# HEAD_IO_RevB.net
KiCad netlist of a schematic drawn in EAGLE
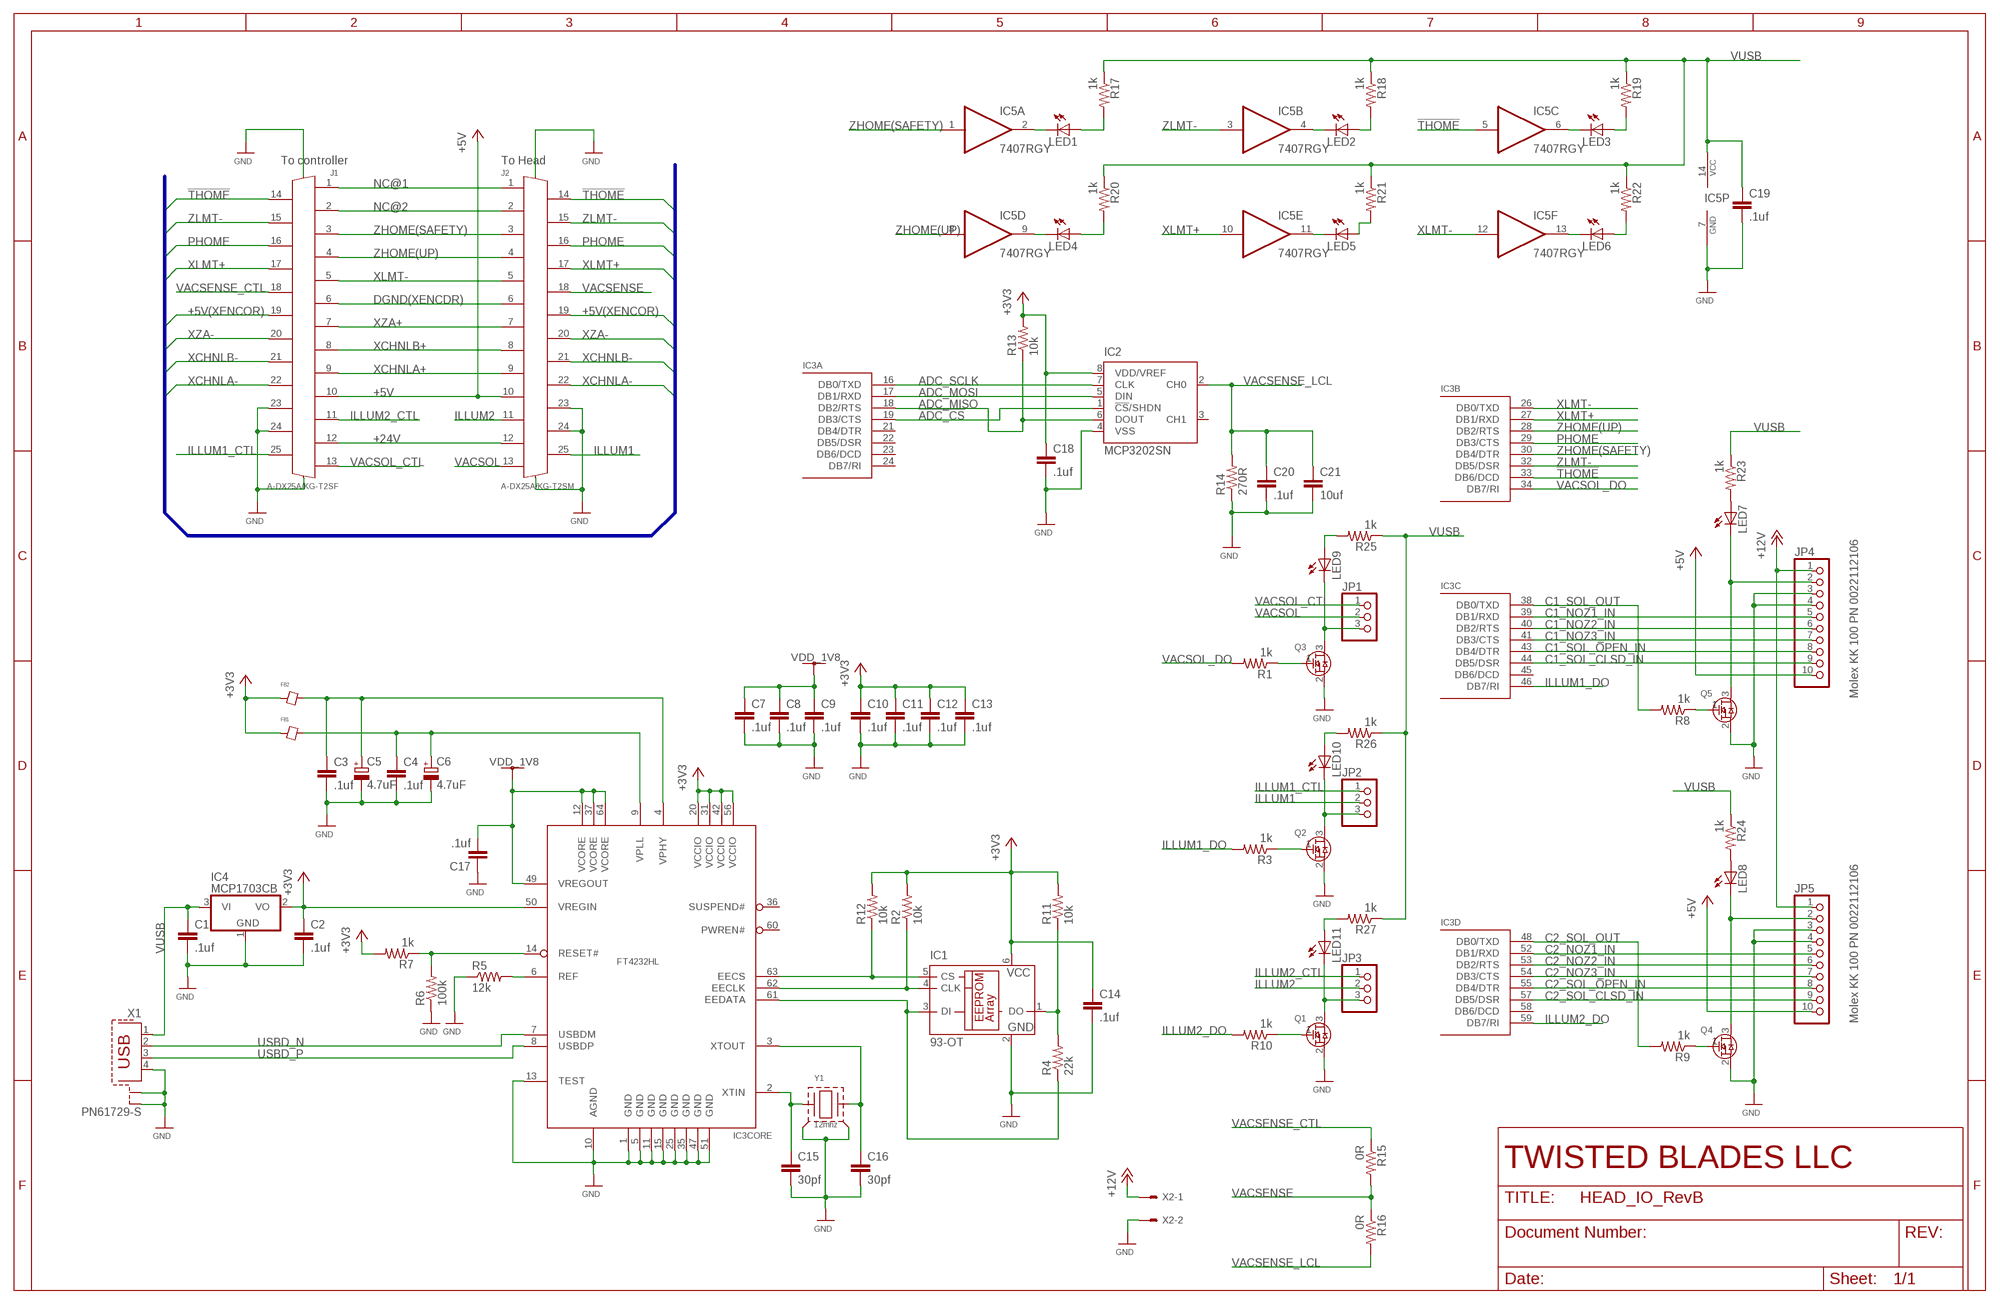
[diagram p0: schematic, sheet 1]

(export (version "E")
  (design (tool "Eeschema 10.0.6"))
  (components
    (comp (ref "C1")
      (value ".1uf")
      (footprint "eagle-import:C0603")
      (libsource (lib "eagle-import") (part "C-EUC0603"))
    )
    (comp (ref "C2")
      (value ".1uf")
      (footprint "eagle-import:C0603")
      (libsource (lib "eagle-import") (part "C-EUC0603"))
    )
    (comp (ref "C3")
      (value ".1uf")
      (footprint "eagle-import:C0603")
      (libsource (lib "eagle-import") (part "C-EUC0603"))
    )
    (comp (ref "C4")
      (value ".1uf")
      (footprint "eagle-import:C0603")
      (libsource (lib "eagle-import") (part "C-EUC0603"))
    )
    (comp (ref "C5")
      (value "4.7uF")
      (footprint "eagle-import:A_3216-18R")
      (libsource (lib "eagle-import") (part "CPOL-EUA/3216-18R"))
    )
    (comp (ref "C6")
      (value "4.7uF")
      (footprint "eagle-import:A_3216-18R")
      (libsource (lib "eagle-import") (part "CPOL-EUA/3216-18R"))
    )
    (comp (ref "C7")
      (value ".1uf")
      (footprint "eagle-import:C0603")
      (libsource (lib "eagle-import") (part "C-EUC0603"))
    )
    (comp (ref "C8")
      (value ".1uf")
      (footprint "eagle-import:C0603")
      (libsource (lib "eagle-import") (part "C-EUC0603"))
    )
    (comp (ref "C9")
      (value ".1uf")
      (footprint "eagle-import:C0603")
      (libsource (lib "eagle-import") (part "C-EUC0603"))
    )
    (comp (ref "C10")
      (value ".1uf")
      (footprint "eagle-import:C0603")
      (libsource (lib "eagle-import") (part "C-EUC0603"))
    )
    (comp (ref "C11")
      (value ".1uf")
      (footprint "eagle-import:C0603")
      (libsource (lib "eagle-import") (part "C-EUC0603"))
    )
    (comp (ref "C12")
      (value ".1uf")
      (footprint "eagle-import:C0603")
      (libsource (lib "eagle-import") (part "C-EUC0603"))
    )
    (comp (ref "C13")
      (value ".1uf")
      (footprint "eagle-import:C0603")
      (libsource (lib "eagle-import") (part "C-EUC0603"))
    )
    (comp (ref "C14")
      (value ".1uf")
      (footprint "eagle-import:C0603")
      (libsource (lib "eagle-import") (part "C-EUC0603"))
    )
    (comp (ref "C15")
      (value "30pf")
      (footprint "eagle-import:C0603")
      (libsource (lib "eagle-import") (part "C-EUC0603"))
    )
    (comp (ref "C16")
      (value "30pf")
      (footprint "eagle-import:C0603")
      (libsource (lib "eagle-import") (part "C-EUC0603"))
    )
    (comp (ref "C17")
      (value ".1uf")
      (footprint "eagle-import:C0603")
      (libsource (lib "eagle-import") (part "C-EUC0603"))
    )
    (comp (ref "C18")
      (value ".1uf")
      (footprint "eagle-import:C0603")
      (libsource (lib "eagle-import") (part "C-EUC0603"))
    )
    (comp (ref "C19")
      (value ".1uf")
      (footprint "eagle-import:C0603")
      (libsource (lib "eagle-import") (part "C-EUC0603"))
    )
    (comp (ref "C20")
      (value ".1uf")
      (footprint "eagle-import:C0603")
      (libsource (lib "eagle-import") (part "C-EUC0603"))
    )
    (comp (ref "C21")
      (value "10uf")
      (footprint "eagle-import:C0805K")
      (libsource (lib "eagle-import") (part "C-EUC0805K"))
    )
    (comp (ref "FB1")
      (value "FERRITE0603")
      (footprint "eagle-import:0603")
      (libsource (lib "eagle-import") (part "FERRITE0603"))
    )
    (comp (ref "FB2")
      (value "FERRITE0603")
      (footprint "eagle-import:0603")
      (libsource (lib "eagle-import") (part "FERRITE0603"))
    )
    (comp (ref "IC1")
      (value "93-OT")
      (footprint "eagle-import:SOT23-6")
      (libsource (lib "eagle-import") (part "93-OT"))
    )
    (comp (ref "IC2")
      (value "MCP3202SN")
      (footprint "eagle-import:SO-08")
      (libsource (lib "eagle-import") (part "MCP3202SN"))
    )
    (comp (ref "IC3")
      (value "FT4232HL")
      (footprint "eagle-import:LQFP64")
      (libsource (lib "eagle-import") (part "FT4232HL"))
    )
    (comp (ref "IC4")
      (value "MCP1703CB")
      (footprint "eagle-import:SOT23")
      (libsource (lib "eagle-import") (part "MCP1703CB"))
    )
    (comp (ref "IC5")
      (value "7407RGY")
      (footprint "eagle-import:TI_VQFN14")
      (libsource (lib "eagle-import") (part "7407RGY"))
    )
    (comp (ref "J1")
      (value "A-DX25A/KG-T2SF")
      (footprint "eagle-import:A-DF25A_KG-T2S")
      (libsource (lib "eagle-import") (part "A-DX25A/KG-T2SF"))
    )
    (comp (ref "J2")
      (value "A-DX25A/KG-T2SM")
      (footprint "eagle-import:A-DS25A_KG-T2S")
      (libsource (lib "eagle-import") (part "A-DX25A/KG-T2SM"))
    )
    (comp (ref "JP1")
      (value "PINHD-1X3")
      (footprint "eagle-import:1X03")
      (libsource (lib "eagle-import") (part "PINHD-1X3"))
    )
    (comp (ref "JP2")
      (value "PINHD-1X3")
      (footprint "eagle-import:1X03")
      (libsource (lib "eagle-import") (part "PINHD-1X3"))
    )
    (comp (ref "JP3")
      (value "PINHD-1X3")
      (footprint "eagle-import:1X03")
      (libsource (lib "eagle-import") (part "PINHD-1X3"))
    )
    (comp (ref "JP4")
      (value "PINHD-1X10")
      (footprint "eagle-import:1X10")
      (libsource (lib "eagle-import") (part "PINHD-1X10"))
    )
    (comp (ref "JP5")
      (value "PINHD-1X10")
      (footprint "eagle-import:1X10")
      (libsource (lib "eagle-import") (part "PINHD-1X10"))
    )
    (comp (ref "LED1")
      (value "LEDCHIP-LED0603")
      (footprint "eagle-import:CHIP-LED0603")
      (libsource (lib "eagle-import") (part "LEDCHIP-LED0603"))
    )
    (comp (ref "LED2")
      (value "LEDCHIP-LED0603")
      (footprint "eagle-import:CHIP-LED0603")
      (libsource (lib "eagle-import") (part "LEDCHIP-LED0603"))
    )
    (comp (ref "LED3")
      (value "LEDCHIP-LED0603")
      (footprint "eagle-import:CHIP-LED0603")
      (libsource (lib "eagle-import") (part "LEDCHIP-LED0603"))
    )
    (comp (ref "LED4")
      (value "LEDCHIP-LED0603")
      (footprint "eagle-import:CHIP-LED0603")
      (libsource (lib "eagle-import") (part "LEDCHIP-LED0603"))
    )
    (comp (ref "LED5")
      (value "LEDCHIP-LED0603")
      (footprint "eagle-import:CHIP-LED0603")
      (libsource (lib "eagle-import") (part "LEDCHIP-LED0603"))
    )
    (comp (ref "LED6")
      (value "LEDCHIP-LED0603")
      (footprint "eagle-import:CHIP-LED0603")
      (libsource (lib "eagle-import") (part "LEDCHIP-LED0603"))
    )
    (comp (ref "LED7")
      (value "LEDCHIP-LED0603")
      (footprint "eagle-import:CHIP-LED0603")
      (libsource (lib "eagle-import") (part "LEDCHIP-LED0603"))
    )
    (comp (ref "LED8")
      (value "LEDCHIP-LED0603")
      (footprint "eagle-import:CHIP-LED0603")
      (libsource (lib "eagle-import") (part "LEDCHIP-LED0603"))
    )
    (comp (ref "LED9")
      (value "LEDCHIP-LED0603")
      (footprint "eagle-import:CHIP-LED0603")
      (libsource (lib "eagle-import") (part "LEDCHIP-LED0603"))
    )
    (comp (ref "LED10")
      (value "LEDCHIP-LED0603")
      (footprint "eagle-import:CHIP-LED0603")
      (libsource (lib "eagle-import") (part "LEDCHIP-LED0603"))
    )
    (comp (ref "LED11")
      (value "LEDCHIP-LED0603")
      (footprint "eagle-import:CHIP-LED0603")
      (libsource (lib "eagle-import") (part "LEDCHIP-LED0603"))
    )
    (comp (ref "Q1")
      (value "FDN86246")
      (footprint "eagle-import:SOT23C")
      (libsource (lib "eagle-import") (part "FDN86246"))
    )
    (comp (ref "Q2")
      (value "FDN86246")
      (footprint "eagle-import:SOT23C")
      (libsource (lib "eagle-import") (part "FDN86246"))
    )
    (comp (ref "Q3")
      (value "FDN86246")
      (footprint "eagle-import:SOT23C")
      (libsource (lib "eagle-import") (part "FDN86246"))
    )
    (comp (ref "Q4")
      (value "FDN86246")
      (footprint "eagle-import:SOT23C")
      (libsource (lib "eagle-import") (part "FDN86246"))
    )
    (comp (ref "Q5")
      (value "FDN86246")
      (footprint "eagle-import:SOT23C")
      (libsource (lib "eagle-import") (part "FDN86246"))
    )
    (comp (ref "R1")
      (value "1k")
      (footprint "eagle-import:R0603")
      (libsource (lib "eagle-import") (part "R-US_R0603"))
    )
    (comp (ref "R2")
      (value "10k")
      (footprint "eagle-import:R0603")
      (libsource (lib "eagle-import") (part "R-US_R0603"))
    )
    (comp (ref "R3")
      (value "1k")
      (footprint "eagle-import:R0603")
      (libsource (lib "eagle-import") (part "R-US_R0603"))
    )
    (comp (ref "R4")
      (value "22k")
      (footprint "eagle-import:R0603")
      (libsource (lib "eagle-import") (part "R-US_R0603"))
    )
    (comp (ref "R5")
      (value "12k")
      (footprint "eagle-import:R0603")
      (libsource (lib "eagle-import") (part "R-US_R0603"))
    )
    (comp (ref "R6")
      (value "100k")
      (footprint "eagle-import:R0603")
      (libsource (lib "eagle-import") (part "R-US_R0603"))
    )
    (comp (ref "R7")
      (value "1k")
      (footprint "eagle-import:R0603")
      (libsource (lib "eagle-import") (part "R-US_R0603"))
    )
    (comp (ref "R8")
      (value "1k")
      (footprint "eagle-import:R0603")
      (libsource (lib "eagle-import") (part "R-US_R0603"))
    )
    (comp (ref "R9")
      (value "1k")
      (footprint "eagle-import:R0603")
      (libsource (lib "eagle-import") (part "R-US_R0603"))
    )
    (comp (ref "R10")
      (value "1k")
      (footprint "eagle-import:R0603")
      (libsource (lib "eagle-import") (part "R-US_R0603"))
    )
    (comp (ref "R11")
      (value "10k")
      (footprint "eagle-import:R0603")
      (libsource (lib "eagle-import") (part "R-US_R0603"))
    )
    (comp (ref "R12")
      (value "10k")
      (footprint "eagle-import:R0603")
      (libsource (lib "eagle-import") (part "R-US_R0603"))
    )
    (comp (ref "R13")
      (value "10k")
      (footprint "eagle-import:R0603")
      (libsource (lib "eagle-import") (part "R-US_R0603"))
    )
    (comp (ref "R14")
      (value "270R")
      (footprint "eagle-import:R0603")
      (libsource (lib "eagle-import") (part "R-US_R0603"))
    )
    (comp (ref "R15")
      (value "0R")
      (footprint "eagle-import:R0603")
      (libsource (lib "eagle-import") (part "R-US_R0603"))
    )
    (comp (ref "R16")
      (value "0R")
      (footprint "eagle-import:R0603")
      (libsource (lib "eagle-import") (part "R-US_R0603"))
    )
    (comp (ref "R17")
      (value "1k")
      (footprint "eagle-import:R0603")
      (libsource (lib "eagle-import") (part "R-US_R0603"))
    )
    (comp (ref "R18")
      (value "1k")
      (footprint "eagle-import:R0603")
      (libsource (lib "eagle-import") (part "R-US_R0603"))
    )
    (comp (ref "R19")
      (value "1k")
      (footprint "eagle-import:R0603")
      (libsource (lib "eagle-import") (part "R-US_R0603"))
    )
    (comp (ref "R20")
      (value "1k")
      (footprint "eagle-import:R0603")
      (libsource (lib "eagle-import") (part "R-US_R0603"))
    )
    (comp (ref "R21")
      (value "1k")
      (footprint "eagle-import:R0603")
      (libsource (lib "eagle-import") (part "R-US_R0603"))
    )
    (comp (ref "R22")
      (value "1k")
      (footprint "eagle-import:R0603")
      (libsource (lib "eagle-import") (part "R-US_R0603"))
    )
    (comp (ref "R23")
      (value "1k")
      (footprint "eagle-import:R0603")
      (libsource (lib "eagle-import") (part "R-US_R0603"))
    )
    (comp (ref "R24")
      (value "1k")
      (footprint "eagle-import:R0603")
      (libsource (lib "eagle-import") (part "R-US_R0603"))
    )
    (comp (ref "R25")
      (value "1k")
      (footprint "eagle-import:R0603")
      (libsource (lib "eagle-import") (part "R-US_R0603"))
    )
    (comp (ref "R26")
      (value "1k")
      (footprint "eagle-import:R0603")
      (libsource (lib "eagle-import") (part "R-US_R0603"))
    )
    (comp (ref "R27")
      (value "1k")
      (footprint "eagle-import:R0603")
      (libsource (lib "eagle-import") (part "R-US_R0603"))
    )
    (comp (ref "X1")
      (value "PN61729-S")
      (footprint "eagle-import:PN61729-S")
      (libsource (lib "eagle-import") (part "PN61729-S"))
    )
    (comp (ref "X2")
      (value "KK-156-2")
      (footprint "eagle-import:KK-156-2")
      (fields (field (name "DIGIKEYPN") "WM50008-02-ND "))
      (libsource (lib "eagle-import") (part "KK-156-2"))
    )
    (comp (ref "Y1")
      (value "12mhz")
      (footprint "eagle-import:ABM8G")
      (libsource (lib "eagle-import") (part "ABM8G"))
    )
  )
  (nets
    (net (code "1") (name "+3V3") (class "Default")
      (node (ref "C10") (pin "1") (pinfunction "1_1") (pintype "passive"))
      (node (ref "C11") (pin "1") (pinfunction "1_1") (pintype "passive"))
      (node (ref "C12") (pin "1") (pinfunction "1_1") (pintype "passive"))
      (node (ref "C13") (pin "1") (pinfunction "1_1") (pintype "passive"))
      (node (ref "C14") (pin "1") (pinfunction "1_1") (pintype "passive"))
      (node (ref "C18") (pin "1") (pinfunction "1_1") (pintype "passive"))
      (node (ref "C2") (pin "1") (pinfunction "1_1") (pintype "passive"))
      (node (ref "FB1") (pin "P$1") (pinfunction "P$1_P$1") (pintype "bidirectional"))
      (node (ref "FB2") (pin "P$1") (pinfunction "P$1_P$1") (pintype "bidirectional"))
      (node (ref "IC1") (pin "6") (pinfunction "VCC_6") (pintype "power_in"))
      (node (ref "IC2") (pin "8") (pinfunction "VDD/VREF_8") (pintype "input"))
      (node (ref "IC3") (pin "20") (pinfunction "VCCIO_20") (pintype "power_in"))
      (node (ref "IC3") (pin "31") (pinfunction "VCCIO_31") (pintype "power_in"))
      (node (ref "IC3") (pin "42") (pinfunction "VCCIO_42") (pintype "power_in"))
      (node (ref "IC3") (pin "50") (pinfunction "VREGIN_50") (pintype "bidirectional"))
      (node (ref "IC3") (pin "56") (pinfunction "VCCIO_56") (pintype "power_in"))
      (node (ref "IC4") (pin "2") (pinfunction "VO_2") (pintype "passive"))
      (node (ref "R11") (pin "2") (pinfunction "2_2") (pintype "passive"))
      (node (ref "R12") (pin "2") (pinfunction "2_2") (pintype "passive"))
      (node (ref "R13") (pin "2") (pinfunction "2_2") (pintype "passive"))
      (node (ref "R2") (pin "2") (pinfunction "2_2") (pintype "passive"))
      (node (ref "R7") (pin "2") (pinfunction "2_2") (pintype "passive"))
    )
    (net (code "2") (name "+5V") (class "Default")
      (node (ref "J1") (pin "10") (pinfunction "10_10") (pintype "bidirectional"))
      (node (ref "J2") (pin "10") (pinfunction "10_10") (pintype "bidirectional"))
      (node (ref "JP4") (pin "10") (pinfunction "10_10") (pintype "passive"))
      (node (ref "JP5") (pin "10") (pinfunction "10_10") (pintype "passive"))
    )
    (net (code "3") (name "+12V") (class "Default")
      (node (ref "JP4") (pin "1") (pinfunction "1_1") (pintype "passive"))
      (node (ref "JP5") (pin "1") (pinfunction "1_1") (pintype "passive"))
      (node (ref "X2") (pin "1") (pinfunction "S_1") (pintype "passive"))
    )
    (net (code "4") (name "/+5V(XENCOR)") (class "Default")
      (node (ref "J1") (pin "19") (pinfunction "19_19") (pintype "bidirectional"))
      (node (ref "J2") (pin "19") (pinfunction "19_19") (pintype "bidirectional"))
    )
    (net (code "5") (name "/+24V") (class "Default")
      (node (ref "J1") (pin "12") (pinfunction "12_12") (pintype "bidirectional"))
      (node (ref "J2") (pin "12") (pinfunction "12_12") (pintype "bidirectional"))
    )
    (net (code "6") (name "/ADC_MISO") (class "Default")
      (node (ref "IC2") (pin "6") (pinfunction "DOUT_6") (pintype "input"))
      (node (ref "IC3") (pin "18") (pinfunction "DB2/RTS_18") (pintype "bidirectional"))
      (node (ref "R13") (pin "1") (pinfunction "1_1") (pintype "passive"))
    )
    (net (code "7") (name "/ADC_MOSI") (class "Default")
      (node (ref "IC2") (pin "5") (pinfunction "DIN_5") (pintype "input"))
      (node (ref "IC3") (pin "17") (pinfunction "DB1/RXD_17") (pintype "bidirectional"))
    )
    (net (code "8") (name "/ADC_SCLK") (class "Default")
      (node (ref "IC2") (pin "7") (pinfunction "CLK_7") (pintype "input"))
      (node (ref "IC3") (pin "16") (pinfunction "DB0/TXD_16") (pintype "bidirectional"))
    )
    (net (code "9") (name "/C1_NOZ1_IN") (class "Default")
      (node (ref "IC3") (pin "39") (pinfunction "DB1/RXD_39") (pintype "bidirectional"))
      (node (ref "JP4") (pin "5") (pinfunction "5_5") (pintype "passive"))
    )
    (net (code "10") (name "/C1_NOZ2_IN") (class "Default")
      (node (ref "IC3") (pin "40") (pinfunction "DB2/RTS_40") (pintype "bidirectional"))
      (node (ref "JP4") (pin "6") (pinfunction "6_6") (pintype "passive"))
    )
    (net (code "11") (name "/C1_NOZ3_IN") (class "Default")
      (node (ref "IC3") (pin "41") (pinfunction "DB3/CTS_41") (pintype "bidirectional"))
      (node (ref "JP4") (pin "7") (pinfunction "7_7") (pintype "passive"))
    )
    (net (code "12") (name "/C1_SOL_CLSD_IN") (class "Default")
      (node (ref "IC3") (pin "44") (pinfunction "DB5/DSR_44") (pintype "bidirectional"))
      (node (ref "JP4") (pin "9") (pinfunction "9_9") (pintype "passive"))
    )
    (net (code "13") (name "/C1_SOL_OPEN_IN") (class "Default")
      (node (ref "IC3") (pin "43") (pinfunction "DB4/DTR_43") (pintype "bidirectional"))
      (node (ref "JP4") (pin "8") (pinfunction "8_8") (pintype "passive"))
    )
    (net (code "14") (name "/C1_SOL_OUT") (class "Default")
      (node (ref "IC3") (pin "38") (pinfunction "DB0/TXD_38") (pintype "bidirectional"))
      (node (ref "R8") (pin "2") (pinfunction "2_2") (pintype "passive"))
    )
    (net (code "15") (name "/C2_NOZ1_IN") (class "Default")
      (node (ref "IC3") (pin "52") (pinfunction "DB1/RXD_52") (pintype "bidirectional"))
      (node (ref "JP5") (pin "5") (pinfunction "5_5") (pintype "passive"))
    )
    (net (code "16") (name "/C2_NOZ2_IN") (class "Default")
      (node (ref "IC3") (pin "53") (pinfunction "DB2/RTS_53") (pintype "bidirectional"))
      (node (ref "JP5") (pin "6") (pinfunction "6_6") (pintype "passive"))
    )
    (net (code "17") (name "/C2_NOZ3_IN") (class "Default")
      (node (ref "IC3") (pin "54") (pinfunction "DB3/CTS_54") (pintype "bidirectional"))
      (node (ref "JP5") (pin "7") (pinfunction "7_7") (pintype "passive"))
    )
    (net (code "18") (name "/C2_SOL_CLSD_IN") (class "Default")
      (node (ref "IC3") (pin "57") (pinfunction "DB5/DSR_57") (pintype "bidirectional"))
      (node (ref "JP5") (pin "9") (pinfunction "9_9") (pintype "passive"))
    )
    (net (code "19") (name "/C2_SOL_OPEN_IN") (class "Default")
      (node (ref "IC3") (pin "55") (pinfunction "DB4/DTR_55") (pintype "bidirectional"))
      (node (ref "JP5") (pin "8") (pinfunction "8_8") (pintype "passive"))
    )
    (net (code "20") (name "/C2_SOL_OUT") (class "Default")
      (node (ref "IC3") (pin "48") (pinfunction "DB0/TXD_48") (pintype "bidirectional"))
      (node (ref "R9") (pin "2") (pinfunction "2_2") (pintype "passive"))
    )
    (net (code "21") (name "/DGND(XENCDR)") (class "Default")
      (node (ref "J1") (pin "6") (pinfunction "6_6") (pintype "bidirectional"))
      (node (ref "J2") (pin "6") (pinfunction "6_6") (pintype "bidirectional"))
    )
    (net (code "22") (name "/ILLUM1") (class "Default")
      (node (ref "J2") (pin "25") (pinfunction "25_25") (pintype "bidirectional"))
      (node (ref "JP2") (pin "2") (pinfunction "2_2") (pintype "passive"))
    )
    (net (code "23") (name "/ILLUM1_CTL") (class "Default")
      (node (ref "J1") (pin "25") (pinfunction "25_25") (pintype "bidirectional"))
      (node (ref "JP2") (pin "1") (pinfunction "1_1") (pintype "passive"))
    )
    (net (code "24") (name "/ILLUM1_DO") (class "Default")
      (node (ref "IC3") (pin "46") (pinfunction "DB7/RI_46") (pintype "bidirectional"))
      (node (ref "R3") (pin "2") (pinfunction "2_2") (pintype "passive"))
    )
    (net (code "25") (name "/ILLUM2") (class "Default")
      (node (ref "J2") (pin "11") (pinfunction "11_11") (pintype "bidirectional"))
      (node (ref "JP3") (pin "2") (pinfunction "2_2") (pintype "passive"))
    )
    (net (code "26") (name "/ILLUM2_CTL") (class "Default")
      (node (ref "J1") (pin "11") (pinfunction "11_11") (pintype "bidirectional"))
      (node (ref "JP3") (pin "1") (pinfunction "1_1") (pintype "passive"))
    )
    (net (code "27") (name "/ILLUM2_DO") (class "Default")
      (node (ref "IC3") (pin "59") (pinfunction "DB7/RI_59") (pintype "bidirectional"))
      (node (ref "R10") (pin "2") (pinfunction "2_2") (pintype "passive"))
    )
    (net (code "28") (name "/NC@1") (class "Default")
      (node (ref "J1") (pin "1") (pinfunction "1_1") (pintype "bidirectional"))
      (node (ref "J2") (pin "1") (pinfunction "1_1") (pintype "bidirectional"))
    )
    (net (code "29") (name "/NC@2") (class "Default")
      (node (ref "J1") (pin "2") (pinfunction "2_2") (pintype "bidirectional"))
      (node (ref "J2") (pin "2") (pinfunction "2_2") (pintype "bidirectional"))
    )
    (net (code "30") (name "/PHOME") (class "Default")
      (node (ref "IC3") (pin "29") (pinfunction "DB3/CTS_29") (pintype "bidirectional"))
      (node (ref "J1") (pin "16") (pinfunction "16_16") (pintype "bidirectional"))
      (node (ref "J2") (pin "16") (pinfunction "16_16") (pintype "bidirectional"))
    )
    (net (code "31") (name "/USBD_N") (class "Default")
      (node (ref "IC3") (pin "7") (pinfunction "USBDM_7") (pintype "input"))
      (node (ref "X1") (pin "2") (pinfunction "2_2") (pintype "passive"))
    )
    (net (code "32") (name "/USBD_P") (class "Default")
      (node (ref "IC3") (pin "8") (pinfunction "USBDP_8") (pintype "input"))
      (node (ref "X1") (pin "3") (pinfunction "3_3") (pintype "passive"))
    )
    (net (code "33") (name "/VACSENSE") (class "Default")
      (node (ref "J2") (pin "18") (pinfunction "18_18") (pintype "bidirectional"))
      (node (ref "R15") (pin "2") (pinfunction "2_2") (pintype "passive"))
      (node (ref "R16") (pin "1") (pinfunction "1_1") (pintype "passive"))
    )
    (net (code "34") (name "/VACSENSE_CTL") (class "Default")
      (node (ref "J1") (pin "18") (pinfunction "18_18") (pintype "bidirectional"))
      (node (ref "R15") (pin "1") (pinfunction "1_1") (pintype "passive"))
    )
    (net (code "35") (name "/VACSENSE_LCL") (class "Default")
      (node (ref "C20") (pin "1") (pinfunction "1_1") (pintype "passive"))
      (node (ref "C21") (pin "1") (pinfunction "1_1") (pintype "passive"))
      (node (ref "IC2") (pin "2") (pinfunction "CH0_2") (pintype "input"))
      (node (ref "R14") (pin "2") (pinfunction "2_2") (pintype "passive"))
      (node (ref "R16") (pin "2") (pinfunction "2_2") (pintype "passive"))
    )
    (net (code "36") (name "/VACSOL") (class "Default")
      (node (ref "J2") (pin "13") (pinfunction "13_13") (pintype "bidirectional"))
      (node (ref "JP1") (pin "2") (pinfunction "2_2") (pintype "passive"))
    )
    (net (code "37") (name "/VACSOL_CTL") (class "Default")
      (node (ref "J1") (pin "13") (pinfunction "13_13") (pintype "bidirectional"))
      (node (ref "JP1") (pin "1") (pinfunction "1_1") (pintype "passive"))
    )
    (net (code "38") (name "/VACSOL_DO") (class "Default")
      (node (ref "IC3") (pin "34") (pinfunction "DB7/RI_34") (pintype "bidirectional"))
      (node (ref "R1") (pin "2") (pinfunction "2_2") (pintype "passive"))
    )
    (net (code "39") (name "/VUSB") (class "Default")
      (node (ref "C1") (pin "1") (pinfunction "1_1") (pintype "passive"))
      (node (ref "C19") (pin "1") (pinfunction "1_1") (pintype "passive"))
      (node (ref "IC4") (pin "3") (pinfunction "VI_3") (pintype "input"))
      (node (ref "IC5") (pin "14") (pinfunction "VCC_14") (pintype "power_in"))
      (node (ref "R17") (pin "1") (pinfunction "1_1") (pintype "passive"))
      (node (ref "R18") (pin "1") (pinfunction "1_1") (pintype "passive"))
      (node (ref "R19") (pin "1") (pinfunction "1_1") (pintype "passive"))
      (node (ref "R20") (pin "1") (pinfunction "1_1") (pintype "passive"))
      (node (ref "R21") (pin "1") (pinfunction "1_1") (pintype "passive"))
      (node (ref "R22") (pin "1") (pinfunction "1_1") (pintype "passive"))
      (node (ref "R23") (pin "1") (pinfunction "1_1") (pintype "passive"))
      (node (ref "R24") (pin "1") (pinfunction "1_1") (pintype "passive"))
      (node (ref "R25") (pin "1") (pinfunction "1_1") (pintype "passive"))
      (node (ref "R26") (pin "1") (pinfunction "1_1") (pintype "passive"))
      (node (ref "R27") (pin "1") (pinfunction "1_1") (pintype "passive"))
      (node (ref "X1") (pin "1") (pinfunction "1_1") (pintype "passive"))
    )
    (net (code "40") (name "/XCHNLA+") (class "Default")
      (node (ref "J1") (pin "9") (pinfunction "9_9") (pintype "bidirectional"))
      (node (ref "J2") (pin "9") (pinfunction "9_9") (pintype "bidirectional"))
    )
    (net (code "41") (name "/XCHNLA-") (class "Default")
      (node (ref "J1") (pin "22") (pinfunction "22_22") (pintype "bidirectional"))
      (node (ref "J2") (pin "22") (pinfunction "22_22") (pintype "bidirectional"))
    )
    (net (code "42") (name "/XCHNLB+") (class "Default")
      (node (ref "J1") (pin "8") (pinfunction "8_8") (pintype "bidirectional"))
      (node (ref "J2") (pin "8") (pinfunction "8_8") (pintype "bidirectional"))
    )
    (net (code "43") (name "/XCHNLB-") (class "Default")
      (node (ref "J1") (pin "21") (pinfunction "21_21") (pintype "bidirectional"))
      (node (ref "J2") (pin "21") (pinfunction "21_21") (pintype "bidirectional"))
    )
    (net (code "44") (name "/XLMT+") (class "Default")
      (node (ref "IC3") (pin "27") (pinfunction "DB1/RXD_27") (pintype "bidirectional"))
      (node (ref "IC5") (pin "10") (pinfunction "I_10") (pintype "input"))
      (node (ref "J1") (pin "17") (pinfunction "17_17") (pintype "bidirectional"))
      (node (ref "J2") (pin "17") (pinfunction "17_17") (pintype "bidirectional"))
    )
    (net (code "45") (name "/XLMT-") (class "Default")
      (node (ref "IC3") (pin "26") (pinfunction "DB0/TXD_26") (pintype "bidirectional"))
      (node (ref "IC5") (pin "12") (pinfunction "I_12") (pintype "input"))
      (node (ref "J1") (pin "5") (pinfunction "5_5") (pintype "bidirectional"))
      (node (ref "J2") (pin "5") (pinfunction "5_5") (pintype "bidirectional"))
    )
    (net (code "46") (name "/XZA+") (class "Default")
      (node (ref "J1") (pin "7") (pinfunction "7_7") (pintype "bidirectional"))
      (node (ref "J2") (pin "7") (pinfunction "7_7") (pintype "bidirectional"))
    )
    (net (code "47") (name "/XZA-") (class "Default")
      (node (ref "J1") (pin "20") (pinfunction "20_20") (pintype "bidirectional"))
      (node (ref "J2") (pin "20") (pinfunction "20_20") (pintype "bidirectional"))
    )
    (net (code "48") (name "/ZHOME(SAFETY)") (class "Default")
      (node (ref "IC3") (pin "30") (pinfunction "DB4/DTR_30") (pintype "bidirectional"))
      (node (ref "IC5") (pin "1") (pinfunction "I_1") (pintype "input"))
      (node (ref "J1") (pin "3") (pinfunction "3_3") (pintype "bidirectional"))
      (node (ref "J2") (pin "3") (pinfunction "3_3") (pintype "bidirectional"))
    )
    (net (code "49") (name "/ZHOME(UP)") (class "Default")
      (node (ref "IC3") (pin "28") (pinfunction "DB2/RTS_28") (pintype "bidirectional"))
      (node (ref "IC5") (pin "8") (pinfunction "I_8") (pintype "input"))
      (node (ref "J1") (pin "4") (pinfunction "4_4") (pintype "bidirectional"))
      (node (ref "J2") (pin "4") (pinfunction "4_4") (pintype "bidirectional"))
    )
    (net (code "50") (name "/ZLMT-") (class "Default")
      (node (ref "IC3") (pin "32") (pinfunction "DB5/DSR_32") (pintype "bidirectional"))
      (node (ref "IC5") (pin "3") (pinfunction "I_3") (pintype "input"))
      (node (ref "J1") (pin "15") (pinfunction "15_15") (pintype "bidirectional"))
      (node (ref "J2") (pin "15") (pinfunction "15_15") (pintype "bidirectional"))
    )
    (net (code "51") (name "/~{ADC_CS}") (class "Default")
      (node (ref "IC2") (pin "1") (pinfunction "~{CS}/SHDN_1") (pintype "input"))
      (node (ref "IC3") (pin "19") (pinfunction "DB3/CTS_19") (pintype "bidirectional"))
    )
    (net (code "52") (name "/~{THOME}") (class "Default")
      (node (ref "IC3") (pin "33") (pinfunction "DB6/DCD_33") (pintype "bidirectional"))
      (node (ref "IC5") (pin "5") (pinfunction "I_5") (pintype "input"))
      (node (ref "J1") (pin "14") (pinfunction "14_14") (pintype "bidirectional"))
      (node (ref "J2") (pin "14") (pinfunction "14_14") (pintype "bidirectional"))
    )
    (net (code "53") (name "GND") (class "Default")
      (node (ref "C1") (pin "2") (pinfunction "2_2") (pintype "passive"))
      (node (ref "C10") (pin "2") (pinfunction "2_2") (pintype "passive"))
      (node (ref "C11") (pin "2") (pinfunction "2_2") (pintype "passive"))
      (node (ref "C12") (pin "2") (pinfunction "2_2") (pintype "passive"))
      (node (ref "C13") (pin "2") (pinfunction "2_2") (pintype "passive"))
      (node (ref "C14") (pin "2") (pinfunction "2_2") (pintype "passive"))
      (node (ref "C15") (pin "2") (pinfunction "2_2") (pintype "passive"))
      (node (ref "C16") (pin "2") (pinfunction "2_2") (pintype "passive"))
      (node (ref "C17") (pin "1") (pinfunction "1_1") (pintype "passive"))
      (node (ref "C18") (pin "2") (pinfunction "2_2") (pintype "passive"))
      (node (ref "C19") (pin "2") (pinfunction "2_2") (pintype "passive"))
      (node (ref "C2") (pin "2") (pinfunction "2_2") (pintype "passive"))
      (node (ref "C20") (pin "2") (pinfunction "2_2") (pintype "passive"))
      (node (ref "C21") (pin "2") (pinfunction "2_2") (pintype "passive"))
      (node (ref "C3") (pin "2") (pinfunction "2_2") (pintype "passive"))
      (node (ref "C4") (pin "2") (pinfunction "2_2") (pintype "passive"))
      (node (ref "C5") (pin "-") (pinfunction "-_-") (pintype "passive"))
      (node (ref "C6") (pin "-") (pinfunction "-_-") (pintype "passive"))
      (node (ref "C7") (pin "2") (pinfunction "2_2") (pintype "passive"))
      (node (ref "C8") (pin "2") (pinfunction "2_2") (pintype "passive"))
      (node (ref "C9") (pin "2") (pinfunction "2_2") (pintype "passive"))
      (node (ref "IC1") (pin "2") (pinfunction "GND_2") (pintype "power_in"))
      (node (ref "IC2") (pin "4") (pinfunction "VSS_4") (pintype "input"))
      (node (ref "IC3") (pin "1") (pinfunction "GND_1") (pintype "power_in"))
      (node (ref "IC3") (pin "10") (pinfunction "AGND_10") (pintype "power_in"))
      (node (ref "IC3") (pin "11") (pinfunction "GND_11") (pintype "power_in"))
      (node (ref "IC3") (pin "13") (pinfunction "TEST_13") (pintype "input"))
      (node (ref "IC3") (pin "15") (pinfunction "GND_15") (pintype "power_in"))
      (node (ref "IC3") (pin "25") (pinfunction "GND_25") (pintype "power_in"))
      (node (ref "IC3") (pin "35") (pinfunction "GND_35") (pintype "power_in"))
      (node (ref "IC3") (pin "47") (pinfunction "GND_47") (pintype "power_in"))
      (node (ref "IC3") (pin "5") (pinfunction "GND_5") (pintype "power_in"))
      (node (ref "IC3") (pin "51") (pinfunction "GND_51") (pintype "power_in"))
      (node (ref "IC4") (pin "1") (pinfunction "GND_1") (pintype "passive"))
      (node (ref "IC5") (pin "7") (pinfunction "GND_7") (pintype "power_in"))
      (node (ref "J1") (pin "23") (pinfunction "23_23") (pintype "bidirectional"))
      (node (ref "J1") (pin "24") (pinfunction "24_24") (pintype "bidirectional"))
      (node (ref "J1") (pin "SHLD@1") (pinfunction "SHLD_SHLD@1") (pintype "bidirectional"))
      (node (ref "J1") (pin "SHLD@2") (pinfunction "SHLD_SHLD@2") (pintype "bidirectional"))
      (node (ref "J2") (pin "23") (pinfunction "23_23") (pintype "bidirectional"))
      (node (ref "J2") (pin "24") (pinfunction "24_24") (pintype "bidirectional"))
      (node (ref "J2") (pin "SHLD@1") (pinfunction "SHLD_SHLD@1") (pintype "bidirectional"))
      (node (ref "J2") (pin "SHLD@2") (pinfunction "SHLD_SHLD@2") (pintype "bidirectional"))
      (node (ref "JP4") (pin "3") (pinfunction "3_3") (pintype "passive"))
      (node (ref "JP4") (pin "4") (pinfunction "4_4") (pintype "passive"))
      (node (ref "JP5") (pin "3") (pinfunction "3_3") (pintype "passive"))
      (node (ref "JP5") (pin "4") (pinfunction "4_4") (pintype "passive"))
      (node (ref "Q1") (pin "2") (pinfunction "S_2") (pintype "bidirectional"))
      (node (ref "Q2") (pin "2") (pinfunction "S_2") (pintype "bidirectional"))
      (node (ref "Q3") (pin "2") (pinfunction "S_2") (pintype "bidirectional"))
      (node (ref "Q4") (pin "2") (pinfunction "S_2") (pintype "bidirectional"))
      (node (ref "Q5") (pin "2") (pinfunction "S_2") (pintype "bidirectional"))
      (node (ref "R14") (pin "1") (pinfunction "1_1") (pintype "passive"))
      (node (ref "R5") (pin "1") (pinfunction "1_1") (pintype "passive"))
      (node (ref "R6") (pin "1") (pinfunction "1_1") (pintype "passive"))
      (node (ref "X1") (pin "4") (pinfunction "4_4") (pintype "passive"))
      (node (ref "X1") (pin "S1") (pinfunction "S1_S1") (pintype "passive"))
      (node (ref "X1") (pin "S2") (pinfunction "S2_S2") (pintype "passive"))
      (node (ref "X2") (pin "2") (pinfunction "S_2") (pintype "passive"))
      (node (ref "Y1") (pin "2") (pinfunction "GND_2") (pintype "bidirectional"))
      (node (ref "Y1") (pin "4") (pinfunction "GND_4") (pintype "bidirectional"))
    )
    (net (code "54") (name "Net-(IC1-CLK)") (class "Default")
      (node (ref "IC1") (pin "4") (pinfunction "CLK_4") (pintype "input"))
      (node (ref "IC3") (pin "62") (pinfunction "EECLK_62") (pintype "output"))
      (node (ref "R2") (pin "1") (pinfunction "1_1") (pintype "passive"))
    )
    (net (code "55") (name "Net-(IC1-CS)") (class "Default")
      (node (ref "IC1") (pin "5") (pinfunction "CS_5") (pintype "input"))
      (node (ref "IC3") (pin "63") (pinfunction "EECS_63") (pintype "bidirectional"))
      (node (ref "R12") (pin "1") (pinfunction "1_1") (pintype "passive"))
    )
    (net (code "56") (name "Net-(IC1-DI)") (class "Default")
      (node (ref "IC1") (pin "3") (pinfunction "DI_3") (pintype "input"))
      (node (ref "IC3") (pin "61") (pinfunction "EEDATA_61") (pintype "bidirectional"))
      (node (ref "R4") (pin "1") (pinfunction "1_1") (pintype "passive"))
    )
    (net (code "57") (name "Net-(IC1-DO)") (class "Default")
      (node (ref "IC1") (pin "1") (pinfunction "DO_1") (pintype "tri_state"))
      (node (ref "R11") (pin "1") (pinfunction "1_1") (pintype "passive"))
      (node (ref "R4") (pin "2") (pinfunction "2_2") (pintype "passive"))
    )
    (net (code "58") (name "Net-(IC3D-REF)") (class "Default")
      (node (ref "IC3") (pin "6") (pinfunction "REF_6") (pintype "input"))
      (node (ref "R5") (pin "2") (pinfunction "2_2") (pintype "passive"))
    )
    (net (code "59") (name "Net-(IC3D-RESET#)") (class "Default")
      (node (ref "IC3") (pin "14") (pinfunction "RESET#_14") (pintype "input"))
      (node (ref "R6") (pin "2") (pinfunction "2_2") (pintype "passive"))
      (node (ref "R7") (pin "1") (pinfunction "1_1") (pintype "passive"))
    )
    (net (code "60") (name "Net-(IC3D-VPHY)") (class "Default")
      (node (ref "C3") (pin "1") (pinfunction "1_1") (pintype "passive"))
      (node (ref "C5") (pin "+") (pinfunction "+_+") (pintype "passive"))
      (node (ref "FB2") (pin "P$2") (pinfunction "P$2_P$2") (pintype "bidirectional"))
      (node (ref "IC3") (pin "4") (pinfunction "VPHY_4") (pintype "power_in"))
    )
    (net (code "61") (name "Net-(IC3D-VPLL)") (class "Default")
      (node (ref "C4") (pin "1") (pinfunction "1_1") (pintype "passive"))
      (node (ref "C6") (pin "+") (pinfunction "+_+") (pintype "passive"))
      (node (ref "FB1") (pin "P$2") (pinfunction "P$2_P$2") (pintype "bidirectional"))
      (node (ref "IC3") (pin "9") (pinfunction "VPLL_9") (pintype "power_in"))
    )
    (net (code "62") (name "Net-(IC3D-XTIN)") (class "Default")
      (node (ref "C15") (pin "1") (pinfunction "1_1") (pintype "passive"))
      (node (ref "IC3") (pin "2") (pinfunction "XTIN_2") (pintype "input"))
      (node (ref "Y1") (pin "1") (pinfunction "P$1_1") (pintype "bidirectional"))
    )
    (net (code "63") (name "Net-(IC3D-XTOUT)") (class "Default")
      (node (ref "C16") (pin "1") (pinfunction "1_1") (pintype "passive"))
      (node (ref "IC3") (pin "3") (pinfunction "XTOUT_3") (pintype "output"))
      (node (ref "Y1") (pin "3") (pinfunction "P$2_3") (pintype "bidirectional"))
    )
    (net (code "64") (name "Net-(IC5A-O)") (class "Default")
      (node (ref "IC5") (pin "2") (pinfunction "O_2") (pintype "open_collector"))
      (node (ref "LED1") (pin "C") (pinfunction "C_C") (pintype "passive"))
    )
    (net (code "65") (name "Net-(IC5B-O)") (class "Default")
      (node (ref "IC5") (pin "4") (pinfunction "O_4") (pintype "open_collector"))
      (node (ref "LED2") (pin "C") (pinfunction "C_C") (pintype "passive"))
    )
    (net (code "66") (name "Net-(IC5C-O)") (class "Default")
      (node (ref "IC5") (pin "6") (pinfunction "O_6") (pintype "open_collector"))
      (node (ref "LED3") (pin "C") (pinfunction "C_C") (pintype "passive"))
    )
    (net (code "67") (name "Net-(IC5D-O)") (class "Default")
      (node (ref "IC5") (pin "9") (pinfunction "O_9") (pintype "open_collector"))
      (node (ref "LED4") (pin "C") (pinfunction "C_C") (pintype "passive"))
    )
    (net (code "68") (name "Net-(IC5E-O)") (class "Default")
      (node (ref "IC5") (pin "11") (pinfunction "O_11") (pintype "open_collector"))
      (node (ref "LED5") (pin "C") (pinfunction "C_C") (pintype "passive"))
    )
    (net (code "69") (name "Net-(IC5F-O)") (class "Default")
      (node (ref "IC5") (pin "13") (pinfunction "O_13") (pintype "open_collector"))
      (node (ref "LED6") (pin "C") (pinfunction "C_C") (pintype "passive"))
    )
    (net (code "70") (name "Net-(LED1-PadA)") (class "Default")
      (node (ref "LED1") (pin "A") (pinfunction "A_A") (pintype "passive"))
      (node (ref "R17") (pin "2") (pinfunction "2_2") (pintype "passive"))
    )
    (net (code "71") (name "Net-(LED2-PadA)") (class "Default")
      (node (ref "LED2") (pin "A") (pinfunction "A_A") (pintype "passive"))
      (node (ref "R18") (pin "2") (pinfunction "2_2") (pintype "passive"))
    )
    (net (code "72") (name "Net-(LED3-PadA)") (class "Default")
      (node (ref "LED3") (pin "A") (pinfunction "A_A") (pintype "passive"))
      (node (ref "R19") (pin "2") (pinfunction "2_2") (pintype "passive"))
    )
    (net (code "73") (name "Net-(LED4-PadA)") (class "Default")
      (node (ref "LED4") (pin "A") (pinfunction "A_A") (pintype "passive"))
      (node (ref "R20") (pin "2") (pinfunction "2_2") (pintype "passive"))
    )
    (net (code "74") (name "Net-(LED5-PadA)") (class "Default")
      (node (ref "LED5") (pin "A") (pinfunction "A_A") (pintype "passive"))
      (node (ref "R21") (pin "2") (pinfunction "2_2") (pintype "passive"))
    )
    (net (code "75") (name "Net-(LED6-PadA)") (class "Default")
      (node (ref "LED6") (pin "A") (pinfunction "A_A") (pintype "passive"))
      (node (ref "R22") (pin "2") (pinfunction "2_2") (pintype "passive"))
    )
    (net (code "76") (name "Net-(LED7-PadA)") (class "Default")
      (node (ref "LED7") (pin "A") (pinfunction "A_A") (pintype "passive"))
      (node (ref "R23") (pin "2") (pinfunction "2_2") (pintype "passive"))
    )
    (net (code "77") (name "Net-(LED8-PadA)") (class "Default")
      (node (ref "LED8") (pin "A") (pinfunction "A_A") (pintype "passive"))
      (node (ref "R24") (pin "2") (pinfunction "2_2") (pintype "passive"))
    )
    (net (code "78") (name "Net-(LED9-PadA)") (class "Default")
      (node (ref "LED9") (pin "A") (pinfunction "A_A") (pintype "passive"))
      (node (ref "R25") (pin "2") (pinfunction "2_2") (pintype "passive"))
    )
    (net (code "79") (name "Net-(LED10-PadA)") (class "Default")
      (node (ref "LED10") (pin "A") (pinfunction "A_A") (pintype "passive"))
      (node (ref "R26") (pin "2") (pinfunction "2_2") (pintype "passive"))
    )
    (net (code "80") (name "Net-(LED11-PadA)") (class "Default")
      (node (ref "LED11") (pin "A") (pinfunction "A_A") (pintype "passive"))
      (node (ref "R27") (pin "2") (pinfunction "2_2") (pintype "passive"))
    )
    (net (code "81") (name "Net-(Q1-D)") (class "Default")
      (node (ref "JP3") (pin "3") (pinfunction "3_3") (pintype "passive"))
      (node (ref "LED11") (pin "C") (pinfunction "C_C") (pintype "passive"))
      (node (ref "Q1") (pin "3") (pinfunction "D_3") (pintype "bidirectional"))
    )
    (net (code "82") (name "Net-(Q1-G)") (class "Default")
      (node (ref "Q1") (pin "1") (pinfunction "G_1") (pintype "bidirectional"))
      (node (ref "R10") (pin "1") (pinfunction "1_1") (pintype "passive"))
    )
    (net (code "83") (name "Net-(Q2-D)") (class "Default")
      (node (ref "JP2") (pin "3") (pinfunction "3_3") (pintype "passive"))
      (node (ref "LED10") (pin "C") (pinfunction "C_C") (pintype "passive"))
      (node (ref "Q2") (pin "3") (pinfunction "D_3") (pintype "bidirectional"))
    )
    (net (code "84") (name "Net-(Q2-G)") (class "Default")
      (node (ref "Q2") (pin "1") (pinfunction "G_1") (pintype "bidirectional"))
      (node (ref "R3") (pin "1") (pinfunction "1_1") (pintype "passive"))
    )
    (net (code "85") (name "Net-(Q3-D)") (class "Default")
      (node (ref "JP1") (pin "3") (pinfunction "3_3") (pintype "passive"))
      (node (ref "LED9") (pin "C") (pinfunction "C_C") (pintype "passive"))
      (node (ref "Q3") (pin "3") (pinfunction "D_3") (pintype "bidirectional"))
    )
    (net (code "86") (name "Net-(Q3-G)") (class "Default")
      (node (ref "Q3") (pin "1") (pinfunction "G_1") (pintype "bidirectional"))
      (node (ref "R1") (pin "1") (pinfunction "1_1") (pintype "passive"))
    )
    (net (code "87") (name "Net-(Q4-D)") (class "Default")
      (node (ref "JP5") (pin "2") (pinfunction "2_2") (pintype "passive"))
      (node (ref "LED8") (pin "C") (pinfunction "C_C") (pintype "passive"))
      (node (ref "Q4") (pin "3") (pinfunction "D_3") (pintype "bidirectional"))
    )
    (net (code "88") (name "Net-(Q4-G)") (class "Default")
      (node (ref "Q4") (pin "1") (pinfunction "G_1") (pintype "bidirectional"))
      (node (ref "R9") (pin "1") (pinfunction "1_1") (pintype "passive"))
    )
    (net (code "89") (name "Net-(Q5-D)") (class "Default")
      (node (ref "JP4") (pin "2") (pinfunction "2_2") (pintype "passive"))
      (node (ref "LED7") (pin "C") (pinfunction "C_C") (pintype "passive"))
      (node (ref "Q5") (pin "3") (pinfunction "D_3") (pintype "bidirectional"))
    )
    (net (code "90") (name "Net-(Q5-G)") (class "Default")
      (node (ref "Q5") (pin "1") (pinfunction "G_1") (pintype "bidirectional"))
      (node (ref "R8") (pin "1") (pinfunction "1_1") (pintype "passive"))
    )
    (net (code "91") (name "VDD_1V8") (class "Default")
      (node (ref "C17") (pin "2") (pinfunction "2_2") (pintype "passive"))
      (node (ref "C7") (pin "1") (pinfunction "1_1") (pintype "passive"))
      (node (ref "C8") (pin "1") (pinfunction "1_1") (pintype "passive"))
      (node (ref "C9") (pin "1") (pinfunction "1_1") (pintype "passive"))
      (node (ref "IC3") (pin "12") (pinfunction "VCORE_12") (pintype "power_in"))
      (node (ref "IC3") (pin "37") (pinfunction "VCORE_37") (pintype "power_in"))
      (node (ref "IC3") (pin "49") (pinfunction "VREGOUT_49") (pintype "output"))
      (node (ref "IC3") (pin "64") (pinfunction "VCORE_64") (pintype "power_in"))
    )
    (net (code "92") (name "unconnected-(IC2-CH1-Pad3)") (class "Default")
      (node (ref "IC2") (pin "3") (pinfunction "CH1_3") (pintype "input"))
    )
    (net (code "93") (name "unconnected-(IC3A-DB4{slash}DTR-Pad21)") (class "Default")
      (node (ref "IC3") (pin "21") (pinfunction "DB4/DTR_21") (pintype "bidirectional"))
    )
    (net (code "94") (name "unconnected-(IC3A-DB5{slash}DSR-Pad22)") (class "Default")
      (node (ref "IC3") (pin "22") (pinfunction "DB5/DSR_22") (pintype "bidirectional"))
    )
    (net (code "95") (name "unconnected-(IC3A-DB6{slash}DCD-Pad23)") (class "Default")
      (node (ref "IC3") (pin "23") (pinfunction "DB6/DCD_23") (pintype "bidirectional"))
    )
    (net (code "96") (name "unconnected-(IC3A-DB7{slash}RI-Pad24)") (class "Default")
      (node (ref "IC3") (pin "24") (pinfunction "DB7/RI_24") (pintype "bidirectional"))
    )
    (net (code "97") (name "unconnected-(IC3C-DB6{slash}DCD-Pad45)") (class "Default")
      (node (ref "IC3") (pin "45") (pinfunction "DB6/DCD_45") (pintype "bidirectional"))
    )
    (net (code "98") (name "unconnected-(IC3D-PWREN#-Pad60)") (class "Default")
      (node (ref "IC3") (pin "60") (pinfunction "PWREN#_60") (pintype "output"))
    )
    (net (code "99") (name "unconnected-(IC3D-SUSPEND#-Pad36)") (class "Default")
      (node (ref "IC3") (pin "36") (pinfunction "SUSPEND#_36") (pintype "output"))
    )
    (net (code "100") (name "unconnected-(IC3E-DB6{slash}DCD-Pad58)") (class "Default")
      (node (ref "IC3") (pin "58") (pinfunction "DB6/DCD_58") (pintype "bidirectional"))
    )
  )
)
